# h_bridge.net
KiCad netlist of a schematic drawn in Altium Designer
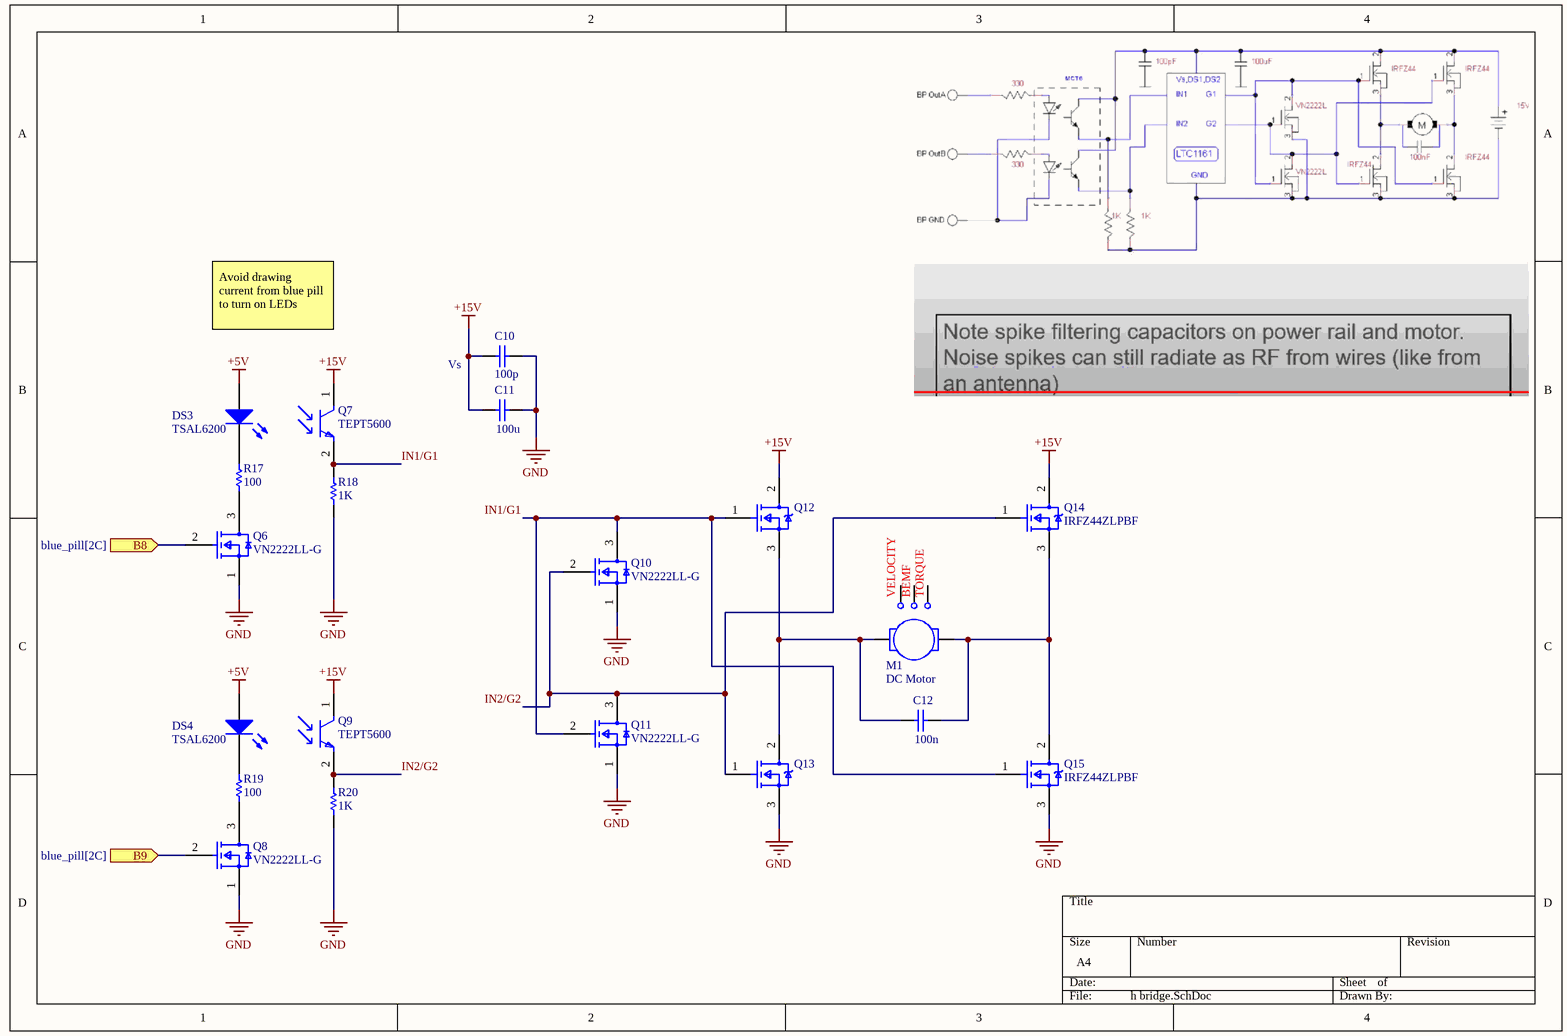
[diagram p0: h bridge.SchDoc]

(export (version "E")
  (design (tool "Eeschema 10.0.6"))
  (components
    (comp (ref "C10")
      (value "100p")
      (description "Capacitor")
      (libsource (lib "Simulation Generic Components") (part "Capacitor"))
    )
    (comp (ref "C11")
      (value "100u")
      (description "Capacitor")
      (libsource (lib "Simulation Generic Components") (part "Capacitor"))
    )
    (comp (ref "C12")
      (value "100n")
      (description "Capacitor")
      (libsource (lib "Simulation Generic Components") (part "Capacitor"))
    )
    (comp (ref "DS3")
      (value "TSAL6200")
      (footprint "VISH-TSAL6200")
      (fields (field (name "MANUFACTURER") "Vishay"))
      (libsource (lib "Altium Content Vault") (part "LED-AK-2"))
    )
    (comp (ref "DS4")
      (value "TSAL6200")
      (footprint "VISH-TSAL6200")
      (fields (field (name "MANUFACTURER") "Vishay"))
      (libsource (lib "Altium Content Vault") (part "LED-AK-2"))
    )
    (comp (ref "M1") (value "DC Motor") (libsource (lib "Simulation Generic Components") (part "DC Motor")))
    (comp (ref "Q6")
      (value "VN2222LL-G")
      (footprint "FP-VN2222LL-G-MFG")
      (description "MOSFET N-CH 60V 0.23A TO92-3")
      (libsource (lib "Altium Content Vault") (part "4ab27c3d3892bfd5e8942bbbfba2a96"))
    )
    (comp (ref "Q7")
      (value "TEPT5600")
      (footprint "FP-6_544-5185_03-4-MFG")
      (description "SENSOR PHOTO 570NM TOP VIEW RAD")
      (libsource (lib "Altium Content Vault") (part "9456f77f46cf90b3cfae45295d5ca59"))
    )
    (comp (ref "Q8")
      (value "VN2222LL-G")
      (footprint "FP-VN2222LL-G-MFG")
      (description "MOSFET N-CH 60V 0.23A TO92-3")
      (libsource (lib "Altium Content Vault") (part "4ab27c3d3892bfd5e8942bbbfba2a96"))
    )
    (comp (ref "Q9")
      (value "TEPT5600")
      (footprint "FP-6_544-5185_03-4-MFG")
      (description "SENSOR PHOTO 570NM TOP VIEW RAD")
      (libsource (lib "Altium Content Vault") (part "9456f77f46cf90b3cfae45295d5ca59"))
    )
    (comp (ref "Q10")
      (value "VN2222LL-G")
      (footprint "FP-VN2222LL-G-MFG")
      (description "MOSFET N-CH 60V 0.23A TO92-3")
      (libsource (lib "Altium Content Vault") (part "4ab27c3d3892bfd5e8942bbbfba2a96"))
    )
    (comp (ref "Q11")
      (value "VN2222LL-G")
      (footprint "FP-VN2222LL-G-MFG")
      (description "MOSFET N-CH 60V 0.23A TO92-3")
      (libsource (lib "Altium Content Vault") (part "4ab27c3d3892bfd5e8942bbbfba2a96"))
    )
    (comp (ref "Q12")
      (value "IRFZ44ZLPBF")
      (footprint "FP-PG-TO262-3-MFG")
      (description "MOSFET N-CH 55V 51A TO262")
      (libsource (lib "Altium Content Vault") (part "b09f7f152735e370c1ea22a33fa83d6"))
    )
    (comp (ref "Q13")
      (value "IRFZ44ZLPBF")
      (footprint "FP-PG-TO262-3-MFG")
      (description "MOSFET N-CH 55V 51A TO262")
      (libsource (lib "Altium Content Vault") (part "b09f7f152735e370c1ea22a33fa83d6"))
    )
    (comp (ref "Q14")
      (value "IRFZ44ZLPBF")
      (footprint "FP-PG-TO262-3-MFG")
      (description "MOSFET N-CH 55V 51A TO262")
      (libsource (lib "Altium Content Vault") (part "b09f7f152735e370c1ea22a33fa83d6"))
    )
    (comp (ref "Q15")
      (value "IRFZ44ZLPBF")
      (footprint "FP-PG-TO262-3-MFG")
      (description "MOSFET N-CH 55V 51A TO262")
      (libsource (lib "Altium Content Vault") (part "b09f7f152735e370c1ea22a33fa83d6"))
    )
    (comp (ref "R17")
      (value "100")
      (description "Resistor")
      (libsource (lib "Simulation Generic Components") (part "Resistor"))
    )
    (comp (ref "R18")
      (value "1K")
      (description "Resistor")
      (libsource (lib "Simulation Generic Components") (part "Resistor"))
    )
    (comp (ref "R19")
      (value "100")
      (description "Resistor")
      (libsource (lib "Simulation Generic Components") (part "Resistor"))
    )
    (comp (ref "R20")
      (value "1K")
      (description "Resistor")
      (libsource (lib "Simulation Generic Components") (part "Resistor"))
    )
  )
  (nets
    (net (code "1") (name "+5V") (class "Default")
      (node (ref "DS3") (pin "1") (pinfunction "A_1") (pintype "passive"))
      (node (ref "DS4") (pin "1") (pinfunction "A_1") (pintype "passive"))
    )
    (net (code "2") (name "+15V") (class "Default")
      (node (ref "C10") (pin "1") (pinfunction "1_1") (pintype "passive"))
      (node (ref "C11") (pin "1") (pinfunction "1_1") (pintype "passive"))
      (node (ref "Q12") (pin "2") (pinfunction "D_2") (pintype "passive"))
      (node (ref "Q14") (pin "2") (pinfunction "D_2") (pintype "passive"))
      (node (ref "Q7") (pin "1") (pinfunction "C_1") (pintype "passive"))
      (node (ref "Q9") (pin "1") (pinfunction "C_1") (pintype "passive"))
    )
    (net (code "3") (name "/B8") (class "Default")
      (node (ref "Q6") (pin "2") (pinfunction "GATE_2") (pintype "passive"))
    )
    (net (code "4") (name "/B9") (class "Default")
      (node (ref "Q8") (pin "2") (pinfunction "GATE_2") (pintype "passive"))
    )
    (net (code "5") (name "/IN1{slash}G1") (class "Default")
      (node (ref "Q10") (pin "3") (pinfunction "DRAIN_3") (pintype "passive"))
      (node (ref "Q11") (pin "2") (pinfunction "GATE_2") (pintype "passive"))
      (node (ref "Q12") (pin "1") (pinfunction "G_1") (pintype "passive"))
      (node (ref "Q15") (pin "1") (pinfunction "G_1") (pintype "passive"))
      (node (ref "Q7") (pin "2") (pinfunction "E_2") (pintype "passive"))
      (node (ref "R18") (pin "1") (pinfunction "1_1") (pintype "passive"))
    )
    (net (code "6") (name "/IN2{slash}G2") (class "Default")
      (node (ref "Q10") (pin "2") (pinfunction "GATE_2") (pintype "passive"))
      (node (ref "Q11") (pin "3") (pinfunction "DRAIN_3") (pintype "passive"))
      (node (ref "Q13") (pin "1") (pinfunction "G_1") (pintype "passive"))
      (node (ref "Q14") (pin "1") (pinfunction "G_1") (pintype "passive"))
      (node (ref "Q9") (pin "2") (pinfunction "E_2") (pintype "passive"))
      (node (ref "R20") (pin "1") (pinfunction "1_1") (pintype "passive"))
    )
    (net (code "7") (name "GND") (class "Default")
      (node (ref "C10") (pin "2") (pinfunction "2_2") (pintype "passive"))
      (node (ref "C11") (pin "2") (pinfunction "2_2") (pintype "passive"))
      (node (ref "Q10") (pin "1") (pinfunction "SOURCE_1") (pintype "passive"))
      (node (ref "Q11") (pin "1") (pinfunction "SOURCE_1") (pintype "passive"))
      (node (ref "Q13") (pin "3") (pinfunction "S_3") (pintype "passive"))
      (node (ref "Q15") (pin "3") (pinfunction "S_3") (pintype "passive"))
      (node (ref "Q6") (pin "1") (pinfunction "SOURCE_1") (pintype "passive"))
      (node (ref "Q8") (pin "1") (pinfunction "SOURCE_1") (pintype "passive"))
      (node (ref "R18") (pin "2") (pinfunction "2_2") (pintype "passive"))
      (node (ref "R20") (pin "2") (pinfunction "2_2") (pintype "passive"))
    )
    (net (code "8") (name "Net-(DS3-K)") (class "Default")
      (node (ref "DS3") (pin "2") (pinfunction "K_2") (pintype "passive"))
      (node (ref "R17") (pin "1") (pinfunction "1_1") (pintype "passive"))
    )
    (net (code "9") (name "Net-(DS4-K)") (class "Default")
      (node (ref "DS4") (pin "2") (pinfunction "K_2") (pintype "passive"))
      (node (ref "R19") (pin "1") (pinfunction "1_1") (pintype "passive"))
    )
    (net (code "10") (name "Net-(Q6-DRAIN)") (class "Default")
      (node (ref "Q6") (pin "3") (pinfunction "DRAIN_3") (pintype "passive"))
      (node (ref "R17") (pin "2") (pinfunction "2_2") (pintype "passive"))
    )
    (net (code "11") (name "Net-(Q8-DRAIN)") (class "Default")
      (node (ref "Q8") (pin "3") (pinfunction "DRAIN_3") (pintype "passive"))
      (node (ref "R19") (pin "2") (pinfunction "2_2") (pintype "passive"))
    )
    (net (code "12") (name "Net-(Q12-S)") (class "Default")
      (node (ref "C12") (pin "1") (pinfunction "1_1") (pintype "passive"))
      (node (ref "M1") (pin "1") (pinfunction "1_1") (pintype "passive"))
      (node (ref "Q12") (pin "3") (pinfunction "S_3") (pintype "passive"))
      (node (ref "Q13") (pin "2") (pinfunction "D_2") (pintype "passive"))
    )
    (net (code "13") (name "Net-(Q14-S)") (class "Default")
      (node (ref "C12") (pin "2") (pinfunction "2_2") (pintype "passive"))
      (node (ref "M1") (pin "2") (pinfunction "2_2") (pintype "passive"))
      (node (ref "Q14") (pin "3") (pinfunction "S_3") (pintype "passive"))
      (node (ref "Q15") (pin "2") (pinfunction "D_2") (pintype "passive"))
    )
    (net (code "14") (name "unconnected-(M1-Pad3)") (class "Default")
      (node (ref "M1") (pin "3") (pinfunction "3_3") (pintype "passive"))
    )
    (net (code "15") (name "unconnected-(M1-Pad4)") (class "Default")
      (node (ref "M1") (pin "4") (pinfunction "4_4") (pintype "passive"))
    )
    (net (code "16") (name "unconnected-(M1-Pad5)") (class "Default")
      (node (ref "M1") (pin "5") (pinfunction "5_5") (pintype "passive"))
    )
  )
)
